# MGNGSQ4_HeaterDongle.net
KiCad netlist of a schematic drawn in Altium Designer
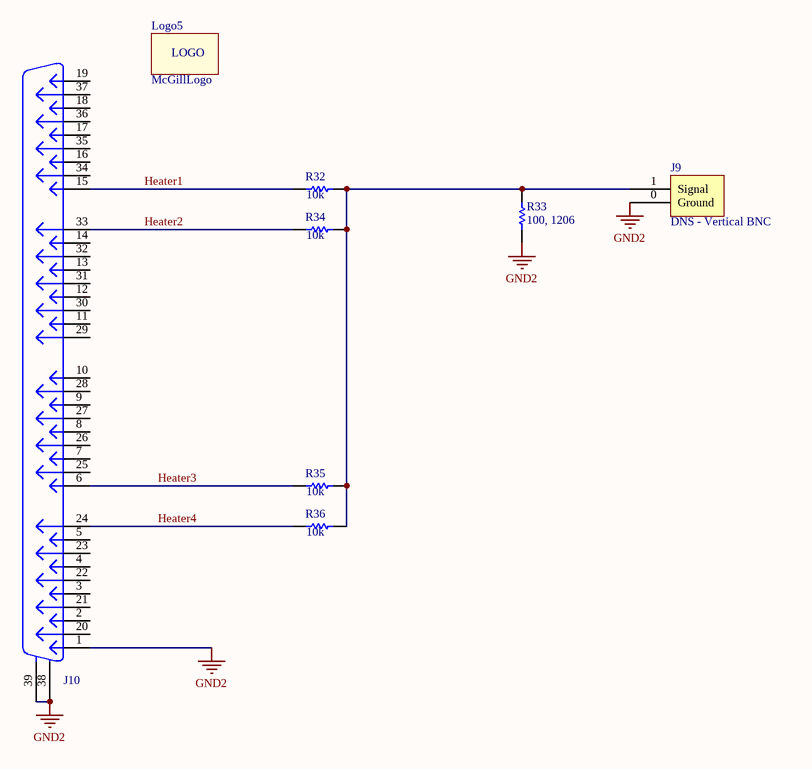
[diagram p0: MGNGSQ4_HeaterDongle.SchDoc]

(export (version "E")
  (design (tool "Eeschema 10.0.6"))
  (components
    (comp (ref "J9")
      (value "DNS - Vertical BNC")
      (footprint "BNCVert")
      (description "Vertical BNC")
      (fields
        (field (name "MANUFACTURER") "TE Connectivity AMP Connectors")
        (field (name "MANUFACTURER PART NUMBER") "5-1634503-1")
      )
      (libsource (lib "MGNGSQ4_Dongles") (part "BNCVertical"))
    )
    (comp (ref "J10")
      (value "DB37M")
      (footprint "DSUB37-M")
      (fields
        (field (name "MANUFACTURER") "Norcomp")
        (field (name "MANUFACTURER PART NUMBER") "182-037-113R531")
      )
      (libsource (lib "MGNGSQ4_Dongles") (part "DB37M"))
    )
    (comp (ref "Logo5")
      (value "McGillLogo")
      (footprint "McGillLogo1")
      (description "Silkscreen Logo")
      (fields (field (name "MANUFACTURER") "McGill"))
      (libsource (lib "MGMEZZ04_Loopback") (part "Logo"))
    )
    (comp (ref "R32")
      (value "10k")
      (footprint "0603")
      (description "10k Ohm RES 0603")
      (fields
        (field (name "MANUFACTURER") "Vishay Dale")
        (field (name "MANUFACTURER PART NUMBER") "CRCW060310K0FKEA")
      )
      (libsource (lib "MGNGSQ4_Dongles") (part "RES 0603"))
    )
    (comp (ref "R33")
      (value "100, 1206")
      (footprint "1206")
      (description "100 Ohm RES 1/4W 1206 SMD")
      (fields
        (field (name "MANUFACTURER") "Rohm Semiconductor")
        (field (name "MANUFACTURER PART NUMBER") "ESR18EZPF1000")
      )
      (libsource (lib "MGNGSQ4_Dongles") (part "RES 1206"))
    )
    (comp (ref "R34")
      (value "10k")
      (footprint "0603")
      (description "10k Ohm RES 0603")
      (fields
        (field (name "MANUFACTURER") "Vishay Dale")
        (field (name "MANUFACTURER PART NUMBER") "CRCW060310K0FKEA")
      )
      (libsource (lib "MGNGSQ4_Dongles") (part "RES 0603"))
    )
    (comp (ref "R35")
      (value "10k")
      (footprint "0603")
      (description "10k Ohm RES 0603")
      (fields
        (field (name "MANUFACTURER") "Vishay Dale")
        (field (name "MANUFACTURER PART NUMBER") "CRCW060310K0FKEA")
      )
      (libsource (lib "MGNGSQ4_Dongles") (part "RES 0603"))
    )
    (comp (ref "R36")
      (value "10k")
      (footprint "0603")
      (description "10k Ohm RES 0603")
      (fields
        (field (name "MANUFACTURER") "Vishay Dale")
        (field (name "MANUFACTURER PART NUMBER") "CRCW060310K0FKEA")
      )
      (libsource (lib "MGNGSQ4_Dongles") (part "RES 0603"))
    )
  )
  (nets
    (net (code "1") (name "/Heater1") (class "Default")
      (node (ref "J10") (pin "15") (pinfunction "15_15") (pintype "passive"))
      (node (ref "R32") (pin "1") (pinfunction "1_1") (pintype "passive"))
    )
    (net (code "2") (name "/Heater2") (class "Default")
      (node (ref "J10") (pin "33") (pinfunction "33_33") (pintype "passive"))
      (node (ref "R34") (pin "1") (pinfunction "1_1") (pintype "passive"))
    )
    (net (code "3") (name "/Heater3") (class "Default")
      (node (ref "J10") (pin "6") (pinfunction "6_6") (pintype "passive"))
      (node (ref "R35") (pin "1") (pinfunction "1_1") (pintype "passive"))
    )
    (net (code "4") (name "/Heater4") (class "Default")
      (node (ref "J10") (pin "24") (pinfunction "24_24") (pintype "passive"))
      (node (ref "R36") (pin "1") (pinfunction "1_1") (pintype "passive"))
    )
    (net (code "5") (name "GND2") (class "Default")
      (node (ref "J10") (pin "1") (pinfunction "1_1") (pintype "passive"))
      (node (ref "J10") (pin "38") (pinfunction "MH1_38") (pintype "passive"))
      (node (ref "J10") (pin "39") (pinfunction "MH2_39") (pintype "passive"))
      (node (ref "J9") (pin "0") (pinfunction "Ground_0") (pintype "passive"))
      (node (ref "R33") (pin "1") (pinfunction "1_1") (pintype "passive"))
    )
    (net (code "6") (name "Net-(J9-Signal)") (class "Default")
      (node (ref "J9") (pin "1") (pinfunction "Signal_1") (pintype "passive"))
      (node (ref "R32") (pin "2") (pinfunction "2_2") (pintype "passive"))
      (node (ref "R33") (pin "2") (pinfunction "2_2") (pintype "passive"))
      (node (ref "R34") (pin "2") (pinfunction "2_2") (pintype "passive"))
      (node (ref "R35") (pin "2") (pinfunction "2_2") (pintype "passive"))
      (node (ref "R36") (pin "2") (pinfunction "2_2") (pintype "passive"))
    )
    (net (code "7") (name "unconnected-(J10-Pad2)") (class "Default")
      (node (ref "J10") (pin "2") (pinfunction "2_2") (pintype "passive"))
    )
    (net (code "8") (name "unconnected-(J10-Pad3)") (class "Default")
      (node (ref "J10") (pin "3") (pinfunction "3_3") (pintype "passive"))
    )
    (net (code "9") (name "unconnected-(J10-Pad4)") (class "Default")
      (node (ref "J10") (pin "4") (pinfunction "4_4") (pintype "passive"))
    )
    (net (code "10") (name "unconnected-(J10-Pad5)") (class "Default")
      (node (ref "J10") (pin "5") (pinfunction "5_5") (pintype "passive"))
    )
    (net (code "11") (name "unconnected-(J10-Pad7)") (class "Default")
      (node (ref "J10") (pin "7") (pinfunction "7_7") (pintype "passive"))
    )
    (net (code "12") (name "unconnected-(J10-Pad8)") (class "Default")
      (node (ref "J10") (pin "8") (pinfunction "8_8") (pintype "passive"))
    )
    (net (code "13") (name "unconnected-(J10-Pad9)") (class "Default")
      (node (ref "J10") (pin "9") (pinfunction "9_9") (pintype "passive"))
    )
    (net (code "14") (name "unconnected-(J10-Pad10)") (class "Default")
      (node (ref "J10") (pin "10") (pinfunction "10_10") (pintype "passive"))
    )
    (net (code "15") (name "unconnected-(J10-Pad11)") (class "Default")
      (node (ref "J10") (pin "11") (pinfunction "11_11") (pintype "passive"))
    )
    (net (code "16") (name "unconnected-(J10-Pad12)") (class "Default")
      (node (ref "J10") (pin "12") (pinfunction "12_12") (pintype "passive"))
    )
    (net (code "17") (name "unconnected-(J10-Pad13)") (class "Default")
      (node (ref "J10") (pin "13") (pinfunction "13_13") (pintype "passive"))
    )
    (net (code "18") (name "unconnected-(J10-Pad14)") (class "Default")
      (node (ref "J10") (pin "14") (pinfunction "14_14") (pintype "passive"))
    )
    (net (code "19") (name "unconnected-(J10-Pad16)") (class "Default")
      (node (ref "J10") (pin "16") (pinfunction "16_16") (pintype "passive"))
    )
    (net (code "20") (name "unconnected-(J10-Pad17)") (class "Default")
      (node (ref "J10") (pin "17") (pinfunction "17_17") (pintype "passive"))
    )
    (net (code "21") (name "unconnected-(J10-Pad18)") (class "Default")
      (node (ref "J10") (pin "18") (pinfunction "18_18") (pintype "passive"))
    )
    (net (code "22") (name "unconnected-(J10-Pad19)") (class "Default")
      (node (ref "J10") (pin "19") (pinfunction "19_19") (pintype "passive"))
    )
    (net (code "23") (name "unconnected-(J10-Pad20)") (class "Default")
      (node (ref "J10") (pin "20") (pinfunction "20_20") (pintype "passive"))
    )
    (net (code "24") (name "unconnected-(J10-Pad21)") (class "Default")
      (node (ref "J10") (pin "21") (pinfunction "21_21") (pintype "passive"))
    )
    (net (code "25") (name "unconnected-(J10-Pad22)") (class "Default")
      (node (ref "J10") (pin "22") (pinfunction "22_22") (pintype "passive"))
    )
    (net (code "26") (name "unconnected-(J10-Pad23)") (class "Default")
      (node (ref "J10") (pin "23") (pinfunction "23_23") (pintype "passive"))
    )
    (net (code "27") (name "unconnected-(J10-Pad25)") (class "Default")
      (node (ref "J10") (pin "25") (pinfunction "25_25") (pintype "passive"))
    )
    (net (code "28") (name "unconnected-(J10-Pad26)") (class "Default")
      (node (ref "J10") (pin "26") (pinfunction "26_26") (pintype "passive"))
    )
    (net (code "29") (name "unconnected-(J10-Pad27)") (class "Default")
      (node (ref "J10") (pin "27") (pinfunction "27_27") (pintype "passive"))
    )
    (net (code "30") (name "unconnected-(J10-Pad28)") (class "Default")
      (node (ref "J10") (pin "28") (pinfunction "28_28") (pintype "passive"))
    )
    (net (code "31") (name "unconnected-(J10-Pad29)") (class "Default")
      (node (ref "J10") (pin "29") (pinfunction "29_29") (pintype "passive"))
    )
    (net (code "32") (name "unconnected-(J10-Pad30)") (class "Default")
      (node (ref "J10") (pin "30") (pinfunction "30_30") (pintype "passive"))
    )
    (net (code "33") (name "unconnected-(J10-Pad31)") (class "Default")
      (node (ref "J10") (pin "31") (pinfunction "31_31") (pintype "passive"))
    )
    (net (code "34") (name "unconnected-(J10-Pad32)") (class "Default")
      (node (ref "J10") (pin "32") (pinfunction "32_32") (pintype "passive"))
    )
    (net (code "35") (name "unconnected-(J10-Pad34)") (class "Default")
      (node (ref "J10") (pin "34") (pinfunction "34_34") (pintype "passive"))
    )
    (net (code "36") (name "unconnected-(J10-Pad35)") (class "Default")
      (node (ref "J10") (pin "35") (pinfunction "35_35") (pintype "passive"))
    )
    (net (code "37") (name "unconnected-(J10-Pad36)") (class "Default")
      (node (ref "J10") (pin "36") (pinfunction "36_36") (pintype "passive"))
    )
    (net (code "38") (name "unconnected-(J10-Pad37)") (class "Default")
      (node (ref "J10") (pin "37") (pinfunction "37_37") (pintype "passive"))
    )
  )
)
